# brain_rev_1.net
KiCad netlist of a schematic drawn in EAGLE
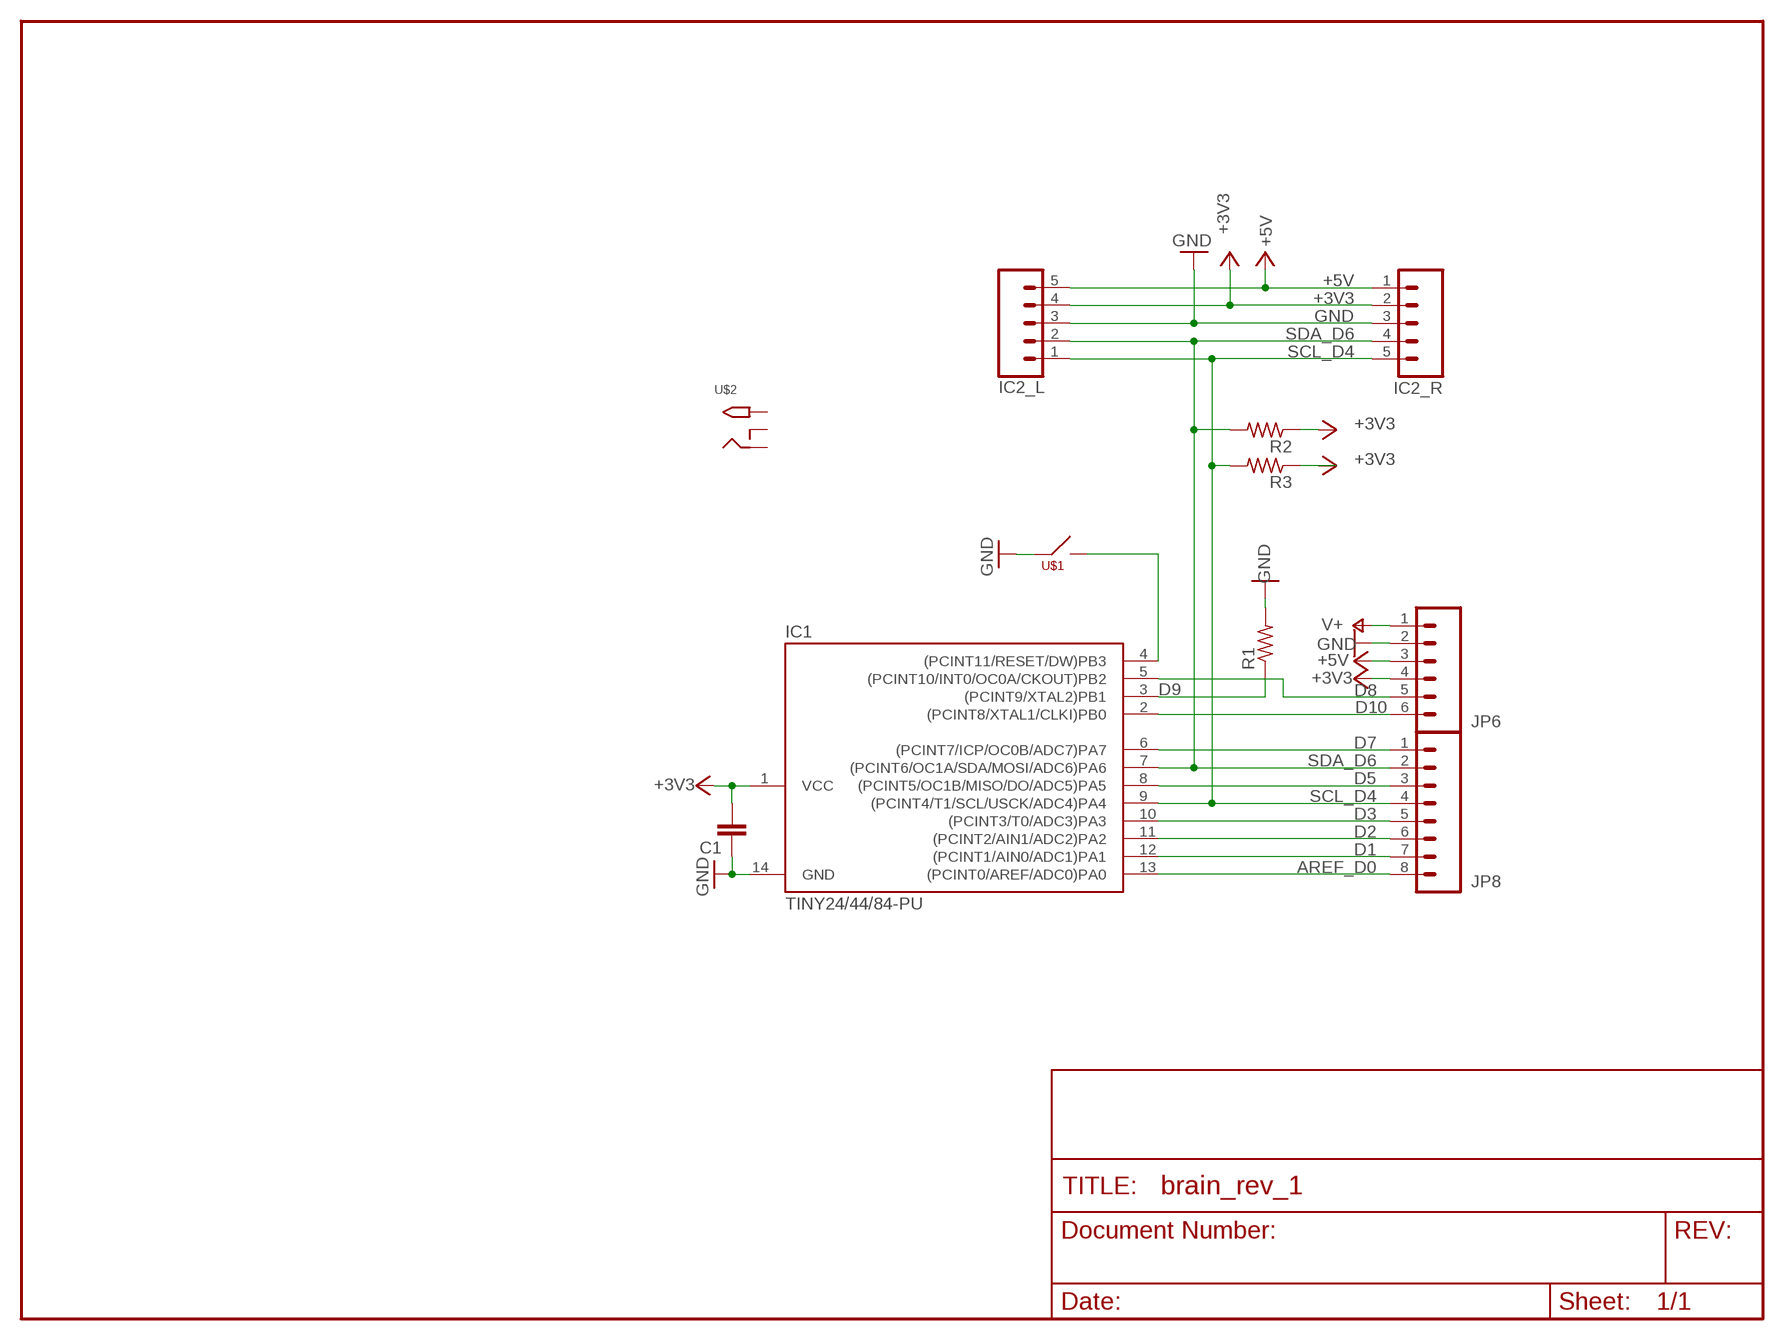
[diagram p0: schematic, sheet 1]

(export (version "E")
  (design (tool "Eeschema 10.0.6"))
  (components
    (comp (ref "C1")
      (value "CAPKIT")
      (footprint "eagle-import:CAP-PTH-SMALL-KIT")
      (libsource (lib "eagle-import") (part "CAPKIT"))
    )
    (comp (ref "IC1")
      (value "TINY24/44/84-PU")
      (footprint "eagle-import:DIL14")
      (libsource (lib "eagle-import") (part "TINY24/44/84-PU"))
    )
    (comp (ref "IC2_L")
      (value "M05PTH")
      (footprint "eagle-import:1X05")
      (libsource (lib "eagle-import") (part "M05PTH"))
    )
    (comp (ref "IC2_R")
      (value "M05PTH")
      (footprint "eagle-import:1X05")
      (libsource (lib "eagle-import") (part "M05PTH"))
    )
    (comp (ref "JP6")
      (value "M06SIP")
      (footprint "eagle-import:1X06")
      (libsource (lib "eagle-import") (part "M06SIP"))
    )
    (comp (ref "JP8")
      (value "M081X08")
      (footprint "eagle-import:1X08")
      (libsource (lib "eagle-import") (part "M081X08"))
    )
    (comp (ref "R1")
      (value "R-US_0204/2V")
      (footprint "eagle-import:0204V")
      (libsource (lib "eagle-import") (part "R-US_0204/2V"))
    )
    (comp (ref "R2")
      (value "R-US_0204/2V")
      (footprint "eagle-import:0204V")
      (libsource (lib "eagle-import") (part "R-US_0204/2V"))
    )
    (comp (ref "R3")
      (value "R-US_0204/2V")
      (footprint "eagle-import:0204V")
      (libsource (lib "eagle-import") (part "R-US_0204/2V"))
    )
    (comp (ref "U$1")
      (value "PTS635_SWITCH")
      (footprint "eagle-import:PTS635_SWITCH")
      (libsource (lib "eagle-import") (part "PTS635_SWITCH"))
    )
    (comp (ref "U$2")
      (value "2.1MMJACKTHM")
      (footprint "eagle-import:PJ-102A")
      (libsource (lib "eagle-import") (part "2.1MMJACKTHM"))
    )
  )
  (nets
    (net (code "1") (name "+3V3") (class "Default")
      (node (ref "C1") (pin "2") (pinfunction "2_2") (pintype "passive"))
      (node (ref "IC1") (pin "1") (pinfunction "VCC_1") (pintype "power_in"))
      (node (ref "IC2_L") (pin "4") (pinfunction "4_4") (pintype "passive"))
      (node (ref "IC2_R") (pin "2") (pinfunction "2_2") (pintype "passive"))
      (node (ref "JP6") (pin "4") (pinfunction "4_4") (pintype "passive"))
      (node (ref "R2") (pin "1") (pinfunction "1_1") (pintype "passive"))
      (node (ref "R3") (pin "1") (pinfunction "1_1") (pintype "passive"))
    )
    (net (code "2") (name "+5V") (class "Default")
      (node (ref "IC2_L") (pin "5") (pinfunction "5_5") (pintype "passive"))
      (node (ref "IC2_R") (pin "1") (pinfunction "1_1") (pintype "passive"))
      (node (ref "JP6") (pin "3") (pinfunction "3_3") (pintype "passive"))
    )
    (net (code "3") (name "/AREF_D0") (class "Default")
      (node (ref "IC1") (pin "13") (pinfunction "(PCINT0/AREF/ADC0)PA0_13") (pintype "bidirectional"))
      (node (ref "JP8") (pin "8") (pinfunction "8_8") (pintype "passive"))
    )
    (net (code "4") (name "/D1") (class "Default")
      (node (ref "IC1") (pin "12") (pinfunction "(PCINT1/AIN0/ADC1)PA1_12") (pintype "bidirectional"))
      (node (ref "JP8") (pin "7") (pinfunction "7_7") (pintype "passive"))
    )
    (net (code "5") (name "/D2") (class "Default")
      (node (ref "IC1") (pin "11") (pinfunction "(PCINT2/AIN1/ADC2)PA2_11") (pintype "bidirectional"))
      (node (ref "JP8") (pin "6") (pinfunction "6_6") (pintype "passive"))
    )
    (net (code "6") (name "/D3") (class "Default")
      (node (ref "IC1") (pin "10") (pinfunction "(PCINT3/T0/ADC3)PA3_10") (pintype "bidirectional"))
      (node (ref "JP8") (pin "5") (pinfunction "5_5") (pintype "passive"))
    )
    (net (code "7") (name "/D5") (class "Default")
      (node (ref "IC1") (pin "8") (pinfunction "(PCINT5/OC1B/MISO/DO/ADC5)PA5_8") (pintype "bidirectional"))
      (node (ref "JP8") (pin "3") (pinfunction "3_3") (pintype "passive"))
    )
    (net (code "8") (name "/D7") (class "Default")
      (node (ref "IC1") (pin "6") (pinfunction "(PCINT7/ICP/OC0B/ADC7)PA7_6") (pintype "bidirectional"))
      (node (ref "JP8") (pin "1") (pinfunction "1_1") (pintype "passive"))
    )
    (net (code "9") (name "/D8") (class "Default")
      (node (ref "IC1") (pin "5") (pinfunction "(PCINT10/INT0/OC0A/CKOUT)PB2_5") (pintype "bidirectional"))
      (node (ref "JP6") (pin "5") (pinfunction "5_5") (pintype "passive"))
    )
    (net (code "10") (name "/D9") (class "Default")
      (node (ref "IC1") (pin "3") (pinfunction "(PCINT9/XTAL2)PB1_3") (pintype "bidirectional"))
      (node (ref "R1") (pin "1") (pinfunction "1_1") (pintype "passive"))
    )
    (net (code "11") (name "/D10") (class "Default")
      (node (ref "IC1") (pin "2") (pinfunction "(PCINT8/XTAL1/CLKI)PB0_2") (pintype "bidirectional"))
      (node (ref "JP6") (pin "6") (pinfunction "6_6") (pintype "passive"))
    )
    (net (code "12") (name "/SCL_D4") (class "Default")
      (node (ref "IC1") (pin "9") (pinfunction "(PCINT4/T1/SCL/USCK/ADC4)PA4_9") (pintype "bidirectional"))
      (node (ref "IC2_L") (pin "1") (pinfunction "1_1") (pintype "passive"))
      (node (ref "IC2_R") (pin "5") (pinfunction "5_5") (pintype "passive"))
      (node (ref "JP8") (pin "4") (pinfunction "4_4") (pintype "passive"))
      (node (ref "R3") (pin "2") (pinfunction "2_2") (pintype "passive"))
    )
    (net (code "13") (name "/SDA_D6") (class "Default")
      (node (ref "IC1") (pin "7") (pinfunction "(PCINT6/OC1A/SDA/MOSI/ADC6)PA6_7") (pintype "bidirectional"))
      (node (ref "IC2_L") (pin "2") (pinfunction "2_2") (pintype "passive"))
      (node (ref "IC2_R") (pin "4") (pinfunction "4_4") (pintype "passive"))
      (node (ref "JP8") (pin "2") (pinfunction "2_2") (pintype "passive"))
      (node (ref "R2") (pin "2") (pinfunction "2_2") (pintype "passive"))
    )
    (net (code "14") (name "GND") (class "Default")
      (node (ref "C1") (pin "1") (pinfunction "1_1") (pintype "passive"))
      (node (ref "IC1") (pin "14") (pinfunction "GND_14") (pintype "power_in"))
      (node (ref "IC2_L") (pin "3") (pinfunction "3_3") (pintype "passive"))
      (node (ref "IC2_R") (pin "3") (pinfunction "3_3") (pintype "passive"))
      (node (ref "JP6") (pin "2") (pinfunction "2_2") (pintype "passive"))
      (node (ref "R1") (pin "2") (pinfunction "2_2") (pintype "passive"))
      (node (ref "U$1") (pin "P$1") (pinfunction "P$1_P$1") (pintype "bidirectional"))
    )
    (net (code "15") (name "Net-(IC1-(PCINT11{slash}RESET{slash}DW)PB3)") (class "Default")
      (node (ref "IC1") (pin "4") (pinfunction "(PCINT11/RESET/DW)PB3_4") (pintype "bidirectional"))
      (node (ref "U$1") (pin "P$2") (pinfunction "P$2_P$2") (pintype "bidirectional"))
    )
    (net (code "16") (name "V+") (class "Default")
      (node (ref "JP6") (pin "1") (pinfunction "1_1") (pintype "passive"))
    )
    (net (code "17") (name "unconnected-(U$2-PadRING)") (class "Default")
      (node (ref "U$2") (pin "RING") (pinfunction "RING_RING") (pintype "bidirectional"))
    )
    (net (code "18") (name "unconnected-(U$2-PadRING_SW)") (class "Default")
      (node (ref "U$2") (pin "RING_SW") (pinfunction "RING_SW_RING_SW") (pintype "bidirectional"))
    )
    (net (code "19") (name "unconnected-(U$2-PadTIP)") (class "Default")
      (node (ref "U$2") (pin "TIP") (pinfunction "TIP_TIP") (pintype "bidirectional"))
    )
  )
)
